# 06_POWER_4.net
KiCad netlist of a schematic drawn in Altium Designer
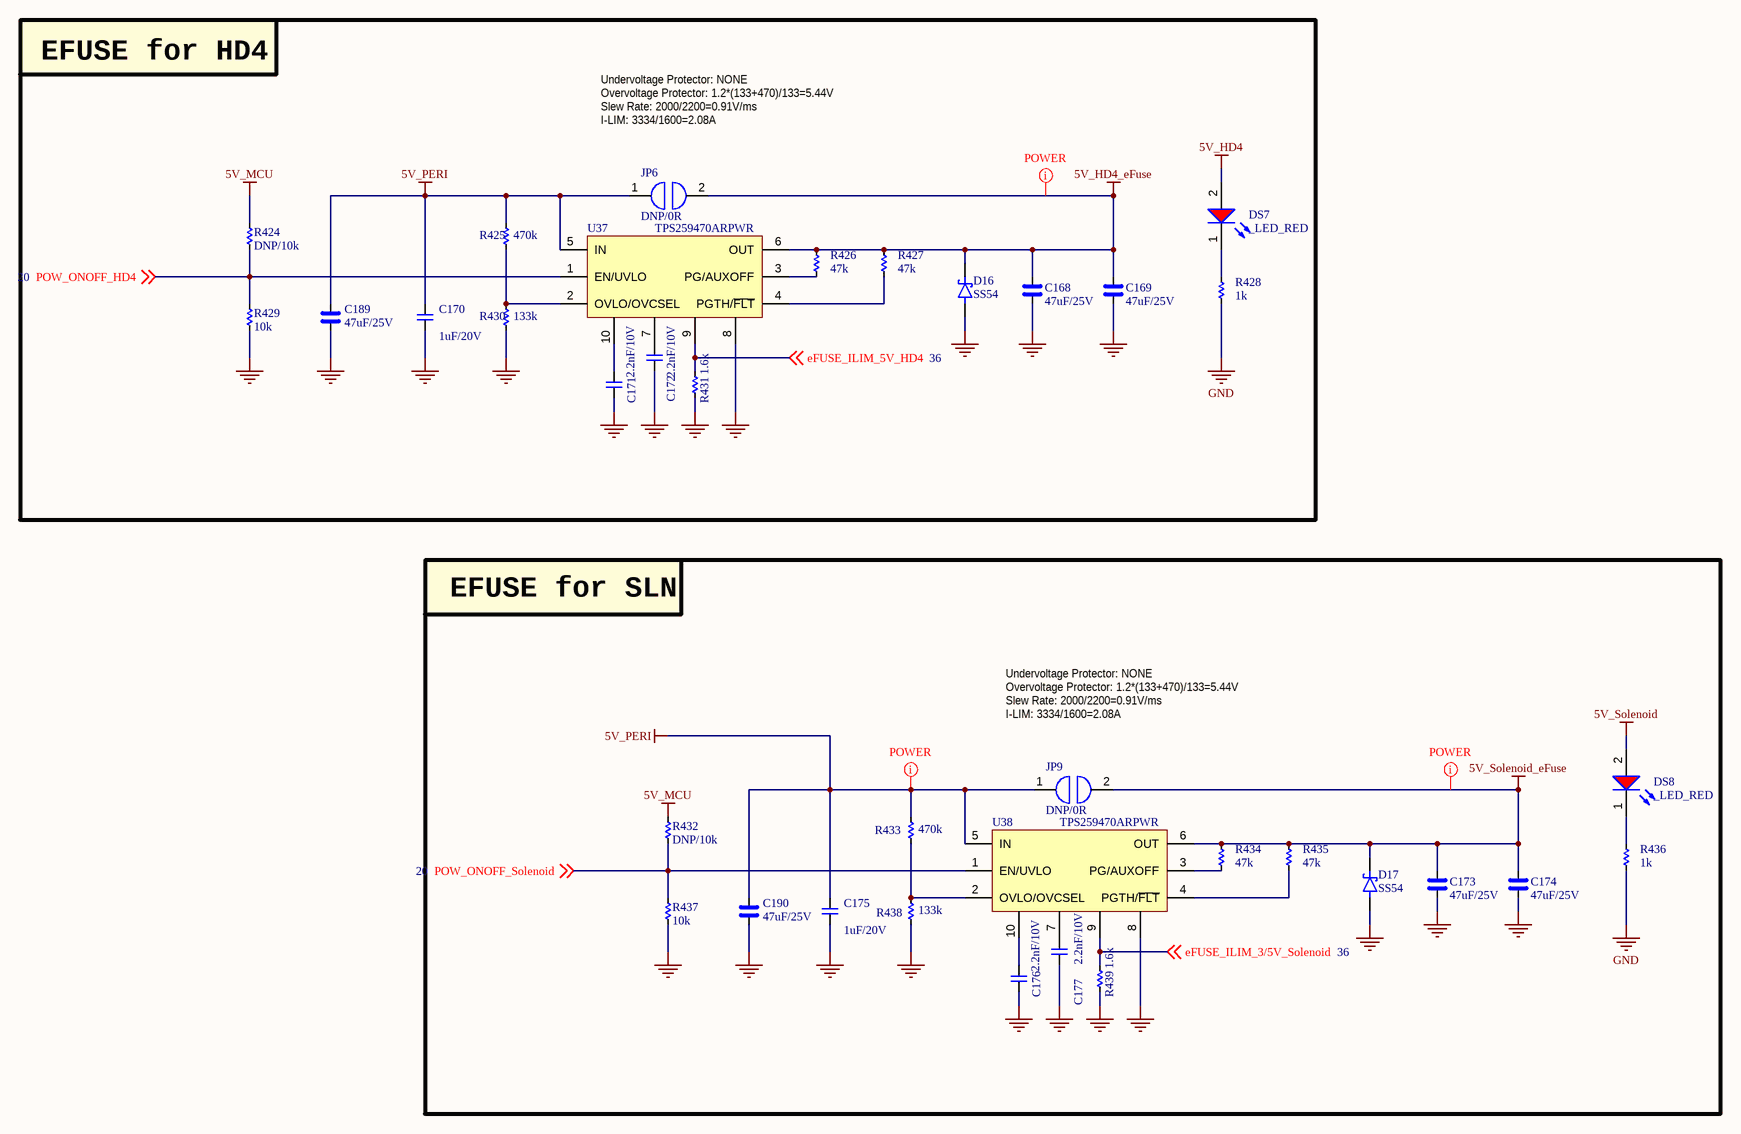
[diagram p0: 06_POWER_4.SchDoc]

(export (version "E")
  (design (tool "Eeschema 10.0.6"))
  (components
    (comp (ref "C168")
      (value "47uF/25V")
      (footprint "CAP_C_3225X80")
      (description "CAP High Value")
      (libsource (lib "LABLIB") (part "_CAP_C_High_2"))
    )
    (comp (ref "C169")
      (value "47uF/25V")
      (footprint "CAP_C_3225X80")
      (description "CAP High Value")
      (libsource (lib "LABLIB") (part "_CAP_C_High_2"))
    )
    (comp (ref "C170")
      (value "1uF/20V")
      (footprint "CAP_C_1005X60")
      (description "CAP")
      (libsource (lib "LABLIB") (part "_CAP_C_2"))
    )
    (comp (ref "C171")
      (value "2.2nF/10V")
      (footprint "CAP_C_1005X60")
      (description "CAP")
      (libsource (lib "LABLIB") (part "_CAP_C_2"))
    )
    (comp (ref "C172")
      (value "2.2nF/10V")
      (footprint "CAP_C_1005X60")
      (description "CAP")
      (libsource (lib "LABLIB") (part "_CAP_C_2"))
    )
    (comp (ref "C173")
      (value "47uF/25V")
      (footprint "CAP_C_3225X80")
      (description "CAP High Value")
      (libsource (lib "LABLIB") (part "_CAP_C_High_2"))
    )
    (comp (ref "C174")
      (value "47uF/25V")
      (footprint "CAP_C_3225X80")
      (description "CAP High Value")
      (libsource (lib "LABLIB") (part "_CAP_C_High_2"))
    )
    (comp (ref "C175")
      (value "1uF/20V")
      (footprint "CAP_C_1005X60")
      (description "CAP")
      (libsource (lib "LABLIB") (part "_CAP_C_2"))
    )
    (comp (ref "C176")
      (value "2.2nF/10V")
      (footprint "CAP_C_1005X60")
      (description "CAP")
      (libsource (lib "LABLIB") (part "_CAP_C_2"))
    )
    (comp (ref "C177")
      (value "2.2nF/10V")
      (footprint "CAP_C_1005X60")
      (description "CAP")
      (libsource (lib "LABLIB") (part "_CAP_C_2"))
    )
    (comp (ref "C189")
      (value "47uF/25V")
      (footprint "CAP_C_3225X80")
      (description "CAP High Value")
      (libsource (lib "LABLIB") (part "_CAP_C_High_2"))
    )
    (comp (ref "C190")
      (value "47uF/25V")
      (footprint "CAP_C_3225X80")
      (description "CAP High Value")
      (libsource (lib "LABLIB") (part "_CAP_C_High_2"))
    )
    (comp (ref "D16")
      (value "SS54")
      (footprint "DO-214AC_SMA")
      (description "DIODE SCHOTTKY")
      (libsource (lib "LABLIB") (part "DIODE SCHOTTKY"))
    )
    (comp (ref "D17")
      (value "SS54")
      (footprint "DO-214AC_SMA")
      (description "DIODE SCHOTTKY")
      (libsource (lib "LABLIB") (part "DIODE SCHOTTKY"))
    )
    (comp (ref "DS7") (value "_LED_RED") (footprint "LED_0603") (libsource (lib "LABLIB") (part "_LED_RED")))
    (comp (ref "DS8") (value "_LED_RED") (footprint "LED_0603") (libsource (lib "LABLIB") (part "_LED_RED")))
    (comp (ref "JP6") (value "DNP/0R") (footprint "JUMPER_1608") (libsource (lib "EXP_V1") (part "JUMPER")))
    (comp (ref "JP9") (value "DNP/0R") (footprint "JUMPER_1608") (libsource (lib "EXP_V1") (part "JUMPER")))
    (comp (ref "R424")
      (value "DNP/10k")
      (footprint "RES_C_1005X40")
      (description "RES")
      (libsource (lib "LABLIB") (part "_RES_B_2"))
    )
    (comp (ref "R425")
      (value "470k")
      (footprint "RES_C_1005X40")
      (description "RES")
      (libsource (lib "LABLIB") (part "_RES_B_2"))
    )
    (comp (ref "R426")
      (value "47k")
      (footprint "RES_C_1005X40")
      (description "RES")
      (libsource (lib "LABLIB") (part "_RES_B_2"))
    )
    (comp (ref "R427")
      (value "47k")
      (footprint "RES_C_1005X40")
      (description "RES")
      (libsource (lib "LABLIB") (part "_RES_B_2"))
    )
    (comp (ref "R428")
      (value "1k")
      (footprint "RES_C_1005X40")
      (description "RES")
      (libsource (lib "LABLIB") (part "_RES_B_2"))
    )
    (comp (ref "R429")
      (value "10k")
      (footprint "RES_C_1005X40")
      (description "RES")
      (libsource (lib "LABLIB") (part "_RES_B_2"))
    )
    (comp (ref "R430")
      (value "133k")
      (footprint "RES_C_1005X40")
      (description "RES")
      (libsource (lib "LABLIB") (part "_RES_B_2"))
    )
    (comp (ref "R431")
      (value "1.6k")
      (footprint "RES_C_1005X40")
      (description "RES")
      (libsource (lib "LABLIB") (part "_RES_B_2"))
    )
    (comp (ref "R432")
      (value "DNP/10k")
      (footprint "RES_C_1005X40")
      (description "RES")
      (libsource (lib "LABLIB") (part "_RES_B_2"))
    )
    (comp (ref "R433")
      (value "470k")
      (footprint "RES_C_1005X40")
      (description "RES")
      (libsource (lib "LABLIB") (part "_RES_B_2"))
    )
    (comp (ref "R434")
      (value "47k")
      (footprint "RES_C_1005X40")
      (description "RES")
      (libsource (lib "LABLIB") (part "_RES_B_2"))
    )
    (comp (ref "R435")
      (value "47k")
      (footprint "RES_C_1005X40")
      (description "RES")
      (libsource (lib "LABLIB") (part "_RES_B_2"))
    )
    (comp (ref "R436")
      (value "1k")
      (footprint "RES_C_1005X40")
      (description "RES")
      (libsource (lib "LABLIB") (part "_RES_B_2"))
    )
    (comp (ref "R437")
      (value "10k")
      (footprint "RES_C_1005X40")
      (description "RES")
      (libsource (lib "LABLIB") (part "_RES_B_2"))
    )
    (comp (ref "R438")
      (value "133k")
      (footprint "RES_C_1005X40")
      (description "RES")
      (libsource (lib "LABLIB") (part "_RES_B_2"))
    )
    (comp (ref "R439")
      (value "1.6k")
      (footprint "RES_C_1005X40")
      (description "RES")
      (libsource (lib "LABLIB") (part "_RES_B_2"))
    )
    (comp (ref "U37")
      (value "TPS259470ARPWR")
      (footprint "VQFN-HR-10")
      (libsource (lib "EXP_HW_V3") (part "TPS259470ARPWR"))
    )
    (comp (ref "U38")
      (value "TPS259470ARPWR")
      (footprint "VQFN-HR-10")
      (libsource (lib "EXP_HW_V3") (part "TPS259470ARPWR"))
    )
  )
  (nets
    (net (code "1") (name "5V_HD4") (class "Default")
      (node (ref "DS7") (pin "2") (pinfunction "A_2") (pintype "passive"))
    )
    (net (code "2") (name "5V_HD4_eFuse") (class "Default")
      (node (ref "C168") (pin "2") (pinfunction "2_2") (pintype "passive"))
      (node (ref "C169") (pin "2") (pinfunction "2_2") (pintype "passive"))
      (node (ref "D16") (pin "1") (pinfunction "K_1") (pintype "passive"))
      (node (ref "JP6") (pin "2") (pinfunction "2_2") (pintype "passive"))
      (node (ref "R426") (pin "2") (pinfunction "2_2") (pintype "passive"))
      (node (ref "R427") (pin "2") (pinfunction "2_2") (pintype "passive"))
      (node (ref "U37") (pin "6") (pinfunction "OUT_6") (pintype "passive"))
    )
    (net (code "3") (name "5V_MCU") (class "Default")
      (node (ref "R424") (pin "1") (pinfunction "1_1") (pintype "passive"))
      (node (ref "R432") (pin "1") (pinfunction "1_1") (pintype "passive"))
    )
    (net (code "4") (name "5V_PERI") (class "Default")
      (node (ref "C170") (pin "2") (pinfunction "2_2") (pintype "passive"))
      (node (ref "C175") (pin "2") (pinfunction "2_2") (pintype "passive"))
      (node (ref "C189") (pin "2") (pinfunction "2_2") (pintype "passive"))
      (node (ref "C190") (pin "2") (pinfunction "2_2") (pintype "passive"))
      (node (ref "JP6") (pin "1") (pinfunction "1_1") (pintype "passive"))
      (node (ref "JP9") (pin "1") (pinfunction "1_1") (pintype "passive"))
      (node (ref "R425") (pin "2") (pinfunction "2_2") (pintype "passive"))
      (node (ref "R433") (pin "2") (pinfunction "2_2") (pintype "passive"))
      (node (ref "U37") (pin "5") (pinfunction "IN_5") (pintype "passive"))
      (node (ref "U38") (pin "5") (pinfunction "IN_5") (pintype "passive"))
    )
    (net (code "5") (name "5V_Solenoid") (class "Default")
      (node (ref "DS8") (pin "2") (pinfunction "A_2") (pintype "passive"))
    )
    (net (code "6") (name "5V_Solenoid_eFuse") (class "Default")
      (node (ref "C173") (pin "2") (pinfunction "2_2") (pintype "passive"))
      (node (ref "C174") (pin "2") (pinfunction "2_2") (pintype "passive"))
      (node (ref "D17") (pin "1") (pinfunction "K_1") (pintype "passive"))
      (node (ref "JP9") (pin "2") (pinfunction "2_2") (pintype "passive"))
      (node (ref "R434") (pin "2") (pinfunction "2_2") (pintype "passive"))
      (node (ref "R435") (pin "2") (pinfunction "2_2") (pintype "passive"))
      (node (ref "U38") (pin "6") (pinfunction "OUT_6") (pintype "passive"))
    )
    (net (code "7") (name "GND") (class "Default")
      (node (ref "C168") (pin "1") (pinfunction "1_1") (pintype "passive"))
      (node (ref "C169") (pin "1") (pinfunction "1_1") (pintype "passive"))
      (node (ref "C170") (pin "1") (pinfunction "1_1") (pintype "passive"))
      (node (ref "C171") (pin "1") (pinfunction "1_1") (pintype "passive"))
      (node (ref "C172") (pin "1") (pinfunction "1_1") (pintype "passive"))
      (node (ref "C173") (pin "1") (pinfunction "1_1") (pintype "passive"))
      (node (ref "C174") (pin "1") (pinfunction "1_1") (pintype "passive"))
      (node (ref "C175") (pin "1") (pinfunction "1_1") (pintype "passive"))
      (node (ref "C176") (pin "1") (pinfunction "1_1") (pintype "passive"))
      (node (ref "C177") (pin "1") (pinfunction "1_1") (pintype "passive"))
      (node (ref "C189") (pin "1") (pinfunction "1_1") (pintype "passive"))
      (node (ref "C190") (pin "1") (pinfunction "1_1") (pintype "passive"))
      (node (ref "D16") (pin "2") (pinfunction "A_2") (pintype "passive"))
      (node (ref "D17") (pin "2") (pinfunction "A_2") (pintype "passive"))
      (node (ref "R428") (pin "1") (pinfunction "1_1") (pintype "passive"))
      (node (ref "R429") (pin "2") (pinfunction "2_2") (pintype "passive"))
      (node (ref "R430") (pin "1") (pinfunction "1_1") (pintype "passive"))
      (node (ref "R431") (pin "1") (pinfunction "1_1") (pintype "passive"))
      (node (ref "R436") (pin "1") (pinfunction "1_1") (pintype "passive"))
      (node (ref "R437") (pin "2") (pinfunction "2_2") (pintype "passive"))
      (node (ref "R438") (pin "1") (pinfunction "1_1") (pintype "passive"))
      (node (ref "R439") (pin "1") (pinfunction "1_1") (pintype "passive"))
      (node (ref "U37") (pin "8") (pinfunction "8_8") (pintype "passive"))
      (node (ref "U38") (pin "8") (pinfunction "8_8") (pintype "passive"))
    )
    (net (code "8") (name "Net-(C171-Pad2)") (class "Default")
      (node (ref "C171") (pin "2") (pinfunction "2_2") (pintype "passive"))
      (node (ref "U37") (pin "10") (pinfunction "10_10") (pintype "passive"))
    )
    (net (code "9") (name "Net-(C172-Pad2)") (class "Default")
      (node (ref "C172") (pin "2") (pinfunction "2_2") (pintype "passive"))
      (node (ref "U37") (pin "7") (pinfunction "7_7") (pintype "passive"))
    )
    (net (code "10") (name "Net-(C176-Pad2)") (class "Default")
      (node (ref "C176") (pin "2") (pinfunction "2_2") (pintype "passive"))
      (node (ref "U38") (pin "10") (pinfunction "10_10") (pintype "passive"))
    )
    (net (code "11") (name "Net-(C177-Pad2)") (class "Default")
      (node (ref "C177") (pin "2") (pinfunction "2_2") (pintype "passive"))
      (node (ref "U38") (pin "7") (pinfunction "7_7") (pintype "passive"))
    )
    (net (code "12") (name "Net-(DS7-K)") (class "Default")
      (node (ref "DS7") (pin "1") (pinfunction "K_1") (pintype "passive"))
      (node (ref "R428") (pin "2") (pinfunction "2_2") (pintype "passive"))
    )
    (net (code "13") (name "Net-(DS8-K)") (class "Default")
      (node (ref "DS8") (pin "1") (pinfunction "K_1") (pintype "passive"))
      (node (ref "R436") (pin "2") (pinfunction "2_2") (pintype "passive"))
    )
    (net (code "14") (name "Net-(U37-OVLO{slash}OVCSEL)") (class "Default")
      (node (ref "R425") (pin "1") (pinfunction "1_1") (pintype "passive"))
      (node (ref "R430") (pin "2") (pinfunction "2_2") (pintype "passive"))
      (node (ref "U37") (pin "2") (pinfunction "OVLO/OVCSEL_2") (pintype "passive"))
    )
    (net (code "15") (name "Net-(U37-PGTH{slash}~{FLT})") (class "Default")
      (node (ref "R427") (pin "1") (pinfunction "1_1") (pintype "passive"))
      (node (ref "U37") (pin "4") (pinfunction "PGTH/~{FLT}_4") (pintype "passive"))
    )
    (net (code "16") (name "Net-(U37-PG{slash}AUXOFF)") (class "Default")
      (node (ref "R426") (pin "1") (pinfunction "1_1") (pintype "passive"))
      (node (ref "U37") (pin "3") (pinfunction "PG/AUXOFF_3") (pintype "passive"))
    )
    (net (code "17") (name "Net-(U38-OVLO{slash}OVCSEL)") (class "Default")
      (node (ref "R433") (pin "1") (pinfunction "1_1") (pintype "passive"))
      (node (ref "R438") (pin "2") (pinfunction "2_2") (pintype "passive"))
      (node (ref "U38") (pin "2") (pinfunction "OVLO/OVCSEL_2") (pintype "passive"))
    )
    (net (code "18") (name "Net-(U38-PGTH{slash}~{FLT})") (class "Default")
      (node (ref "R435") (pin "1") (pinfunction "1_1") (pintype "passive"))
      (node (ref "U38") (pin "4") (pinfunction "PGTH/~{FLT}_4") (pintype "passive"))
    )
    (net (code "19") (name "Net-(U38-PG{slash}AUXOFF)") (class "Default")
      (node (ref "R434") (pin "1") (pinfunction "1_1") (pintype "passive"))
      (node (ref "U38") (pin "3") (pinfunction "PG/AUXOFF_3") (pintype "passive"))
    )
    (net (code "20") (name "POW_ONOFF_HD4") (class "Default")
      (node (ref "R424") (pin "2") (pinfunction "2_2") (pintype "passive"))
      (node (ref "R429") (pin "1") (pinfunction "1_1") (pintype "passive"))
      (node (ref "U37") (pin "1") (pinfunction "EN/UVLO_1") (pintype "passive"))
    )
    (net (code "21") (name "POW_ONOFF_Solenoid") (class "Default")
      (node (ref "R432") (pin "2") (pinfunction "2_2") (pintype "passive"))
      (node (ref "R437") (pin "1") (pinfunction "1_1") (pintype "passive"))
      (node (ref "U38") (pin "1") (pinfunction "EN/UVLO_1") (pintype "passive"))
    )
    (net (code "22") (name "eFUSE_ILIM_3{slash}5V_Solenoid") (class "Default")
      (node (ref "R439") (pin "2") (pinfunction "2_2") (pintype "passive"))
      (node (ref "U38") (pin "9") (pinfunction "9_9") (pintype "passive"))
    )
    (net (code "23") (name "eFUSE_ILIM_5V_HD4") (class "Default")
      (node (ref "R431") (pin "2") (pinfunction "2_2") (pintype "passive"))
      (node (ref "U37") (pin "9") (pinfunction "9_9") (pintype "passive"))
    )
  )
)
